# M217X.net
KiCad netlist of a schematic drawn in EAGLE
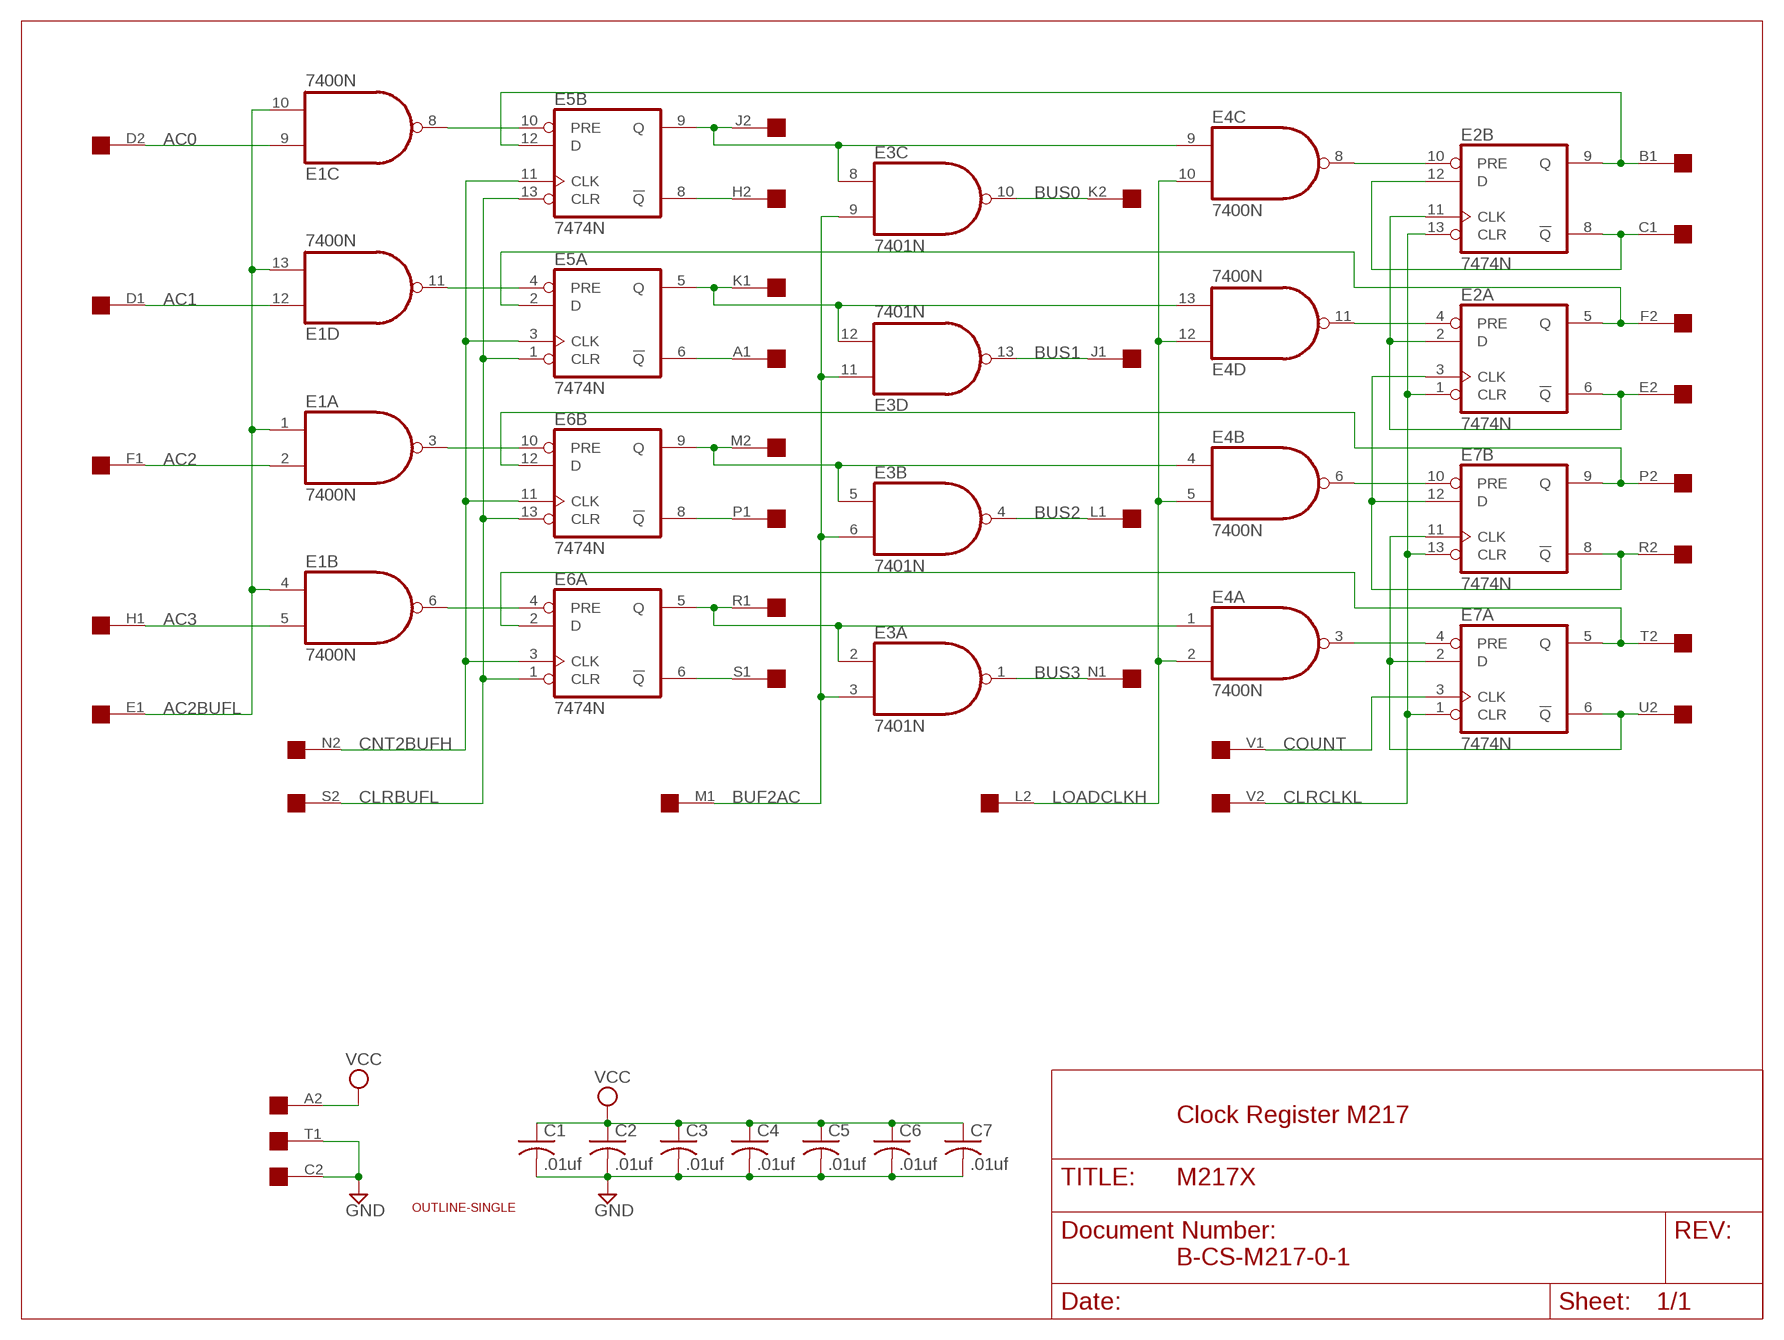
[diagram p0: schematic, sheet 1]

(export (version "E")
  (design (tool "Eeschema 10.0.6"))
  (components
    (comp (ref "C1")
      (value ".01uf")
      (footprint "eagle-import:C050-025X075")
      (libsource (lib "eagle-import") (part "C-US050-025X075"))
    )
    (comp (ref "C2")
      (value ".01uf")
      (footprint "eagle-import:C050-025X075")
      (libsource (lib "eagle-import") (part "C-US050-025X075"))
    )
    (comp (ref "C3")
      (value ".01uf")
      (footprint "eagle-import:C050-025X075")
      (libsource (lib "eagle-import") (part "C-US050-025X075"))
    )
    (comp (ref "C4")
      (value ".01uf")
      (footprint "eagle-import:C050-025X075")
      (libsource (lib "eagle-import") (part "C-US050-025X075"))
    )
    (comp (ref "C5")
      (value ".01uf")
      (footprint "eagle-import:C050-025X075")
      (libsource (lib "eagle-import") (part "C-US050-025X075"))
    )
    (comp (ref "C6")
      (value ".01uf")
      (footprint "eagle-import:C050-025X075")
      (libsource (lib "eagle-import") (part "C-US050-025X075"))
    )
    (comp (ref "C7")
      (value ".01uf")
      (footprint "eagle-import:C050-025X075")
      (libsource (lib "eagle-import") (part "C-US050-025X075"))
    )
    (comp (ref "E1")
      (value "7400N")
      (footprint "eagle-import:DIL14")
      (libsource (lib "eagle-import") (part "7400N"))
    )
    (comp (ref "E2")
      (value "7474N")
      (footprint "eagle-import:DIL14")
      (libsource (lib "eagle-import") (part "7474NS"))
    )
    (comp (ref "E3")
      (value "7401N")
      (footprint "eagle-import:DIL14")
      (libsource (lib "eagle-import") (part "7401NLS"))
    )
    (comp (ref "E4")
      (value "7400N")
      (footprint "eagle-import:DIL14")
      (libsource (lib "eagle-import") (part "7400N"))
    )
    (comp (ref "E5")
      (value "7474N")
      (footprint "eagle-import:DIL14")
      (libsource (lib "eagle-import") (part "7474NS"))
    )
    (comp (ref "E6")
      (value "7474N")
      (footprint "eagle-import:DIL14")
      (libsource (lib "eagle-import") (part "7474NS"))
    )
    (comp (ref "E7")
      (value "7474N")
      (footprint "eagle-import:DIL14")
      (libsource (lib "eagle-import") (part "7474NS"))
    )
    (comp (ref "U$1")
      (value "OUTLINE-SINGLE")
      (footprint "eagle-import:SINGLE")
      (libsource (lib "eagle-import") (part "OUTLINE-SINGLE"))
    )
    (comp (ref "U$4")
      (value "SINGLE")
      (footprint "eagle-import:EDGE-CON2")
      (libsource (lib "eagle-import") (part "SINGLE"))
    )
  )
  (nets
    (net (code "1") (name "/AC0") (class "Default")
      (node (ref "E1") (pin "9") (pinfunction "I0_9") (pintype "input"))
      (node (ref "U$4") (pin "D2") (pinfunction "1_D2") (pintype "bidirectional"))
    )
    (net (code "2") (name "/AC1") (class "Default")
      (node (ref "E1") (pin "12") (pinfunction "I0_12") (pintype "input"))
      (node (ref "U$4") (pin "D1") (pinfunction "1_D1") (pintype "bidirectional"))
    )
    (net (code "3") (name "/AC2") (class "Default")
      (node (ref "E1") (pin "2") (pinfunction "I1_2") (pintype "input"))
      (node (ref "U$4") (pin "F1") (pinfunction "1_F1") (pintype "bidirectional"))
    )
    (net (code "4") (name "/AC2BUFL") (class "Default")
      (node (ref "E1") (pin "1") (pinfunction "I0_1") (pintype "input"))
      (node (ref "E1") (pin "10") (pinfunction "I1_10") (pintype "input"))
      (node (ref "E1") (pin "13") (pinfunction "I1_13") (pintype "input"))
      (node (ref "E1") (pin "4") (pinfunction "I0_4") (pintype "input"))
      (node (ref "U$4") (pin "E1") (pinfunction "1_E1") (pintype "bidirectional"))
    )
    (net (code "5") (name "/AC3") (class "Default")
      (node (ref "E1") (pin "5") (pinfunction "I1_5") (pintype "input"))
      (node (ref "U$4") (pin "H1") (pinfunction "1_H1") (pintype "bidirectional"))
    )
    (net (code "6") (name "/BUF2AC") (class "Default")
      (node (ref "E3") (pin "11") (pinfunction "I0_11") (pintype "input"))
      (node (ref "E3") (pin "3") (pinfunction "I1_3") (pintype "input"))
      (node (ref "E3") (pin "6") (pinfunction "I1_6") (pintype "input"))
      (node (ref "E3") (pin "9") (pinfunction "I1_9") (pintype "input"))
      (node (ref "U$4") (pin "M1") (pinfunction "1_M1") (pintype "bidirectional"))
    )
    (net (code "7") (name "/BUS0") (class "Default")
      (node (ref "E3") (pin "10") (pinfunction "O_10") (pintype "open_collector"))
      (node (ref "U$4") (pin "K2") (pinfunction "1_K2") (pintype "bidirectional"))
    )
    (net (code "8") (name "/BUS1") (class "Default")
      (node (ref "E3") (pin "13") (pinfunction "O_13") (pintype "open_collector"))
      (node (ref "U$4") (pin "J1") (pinfunction "1_J1") (pintype "bidirectional"))
    )
    (net (code "9") (name "/BUS2") (class "Default")
      (node (ref "E3") (pin "4") (pinfunction "O_4") (pintype "open_collector"))
      (node (ref "U$4") (pin "L1") (pinfunction "1_L1") (pintype "bidirectional"))
    )
    (net (code "10") (name "/BUS3") (class "Default")
      (node (ref "E3") (pin "1") (pinfunction "O_1") (pintype "open_collector"))
      (node (ref "U$4") (pin "N1") (pinfunction "1_N1") (pintype "bidirectional"))
    )
    (net (code "11") (name "/CLRBUFL") (class "Default")
      (node (ref "E5") (pin "1") (pinfunction "CLR_1") (pintype "input"))
      (node (ref "E5") (pin "13") (pinfunction "CLR_13") (pintype "input"))
      (node (ref "E6") (pin "1") (pinfunction "CLR_1") (pintype "input"))
      (node (ref "E6") (pin "13") (pinfunction "CLR_13") (pintype "input"))
      (node (ref "U$4") (pin "S2") (pinfunction "1_S2") (pintype "bidirectional"))
    )
    (net (code "12") (name "/CLRCLKL") (class "Default")
      (node (ref "E2") (pin "1") (pinfunction "CLR_1") (pintype "input"))
      (node (ref "E2") (pin "13") (pinfunction "CLR_13") (pintype "input"))
      (node (ref "E7") (pin "1") (pinfunction "CLR_1") (pintype "input"))
      (node (ref "E7") (pin "13") (pinfunction "CLR_13") (pintype "input"))
      (node (ref "U$4") (pin "V2") (pinfunction "1_V2") (pintype "bidirectional"))
    )
    (net (code "13") (name "/CNT2BUFH") (class "Default")
      (node (ref "E5") (pin "11") (pinfunction "CLK_11") (pintype "input"))
      (node (ref "E5") (pin "3") (pinfunction "CLK_3") (pintype "input"))
      (node (ref "E6") (pin "11") (pinfunction "CLK_11") (pintype "input"))
      (node (ref "E6") (pin "3") (pinfunction "CLK_3") (pintype "input"))
      (node (ref "U$4") (pin "N2") (pinfunction "1_N2") (pintype "bidirectional"))
    )
    (net (code "14") (name "/COUNT") (class "Default")
      (node (ref "E7") (pin "3") (pinfunction "CLK_3") (pintype "input"))
      (node (ref "U$4") (pin "V1") (pinfunction "1_V1") (pintype "bidirectional"))
    )
    (net (code "15") (name "/LOADCLKH") (class "Default")
      (node (ref "E4") (pin "10") (pinfunction "I1_10") (pintype "input"))
      (node (ref "E4") (pin "12") (pinfunction "I0_12") (pintype "input"))
      (node (ref "E4") (pin "2") (pinfunction "I1_2") (pintype "input"))
      (node (ref "E4") (pin "5") (pinfunction "I1_5") (pintype "input"))
      (node (ref "U$4") (pin "L2") (pinfunction "1_L2") (pintype "bidirectional"))
    )
    (net (code "16") (name "GND") (class "Default")
      (node (ref "C1") (pin "2") (pinfunction "2_2") (pintype "passive"))
      (node (ref "C2") (pin "2") (pinfunction "2_2") (pintype "passive"))
      (node (ref "C3") (pin "2") (pinfunction "2_2") (pintype "passive"))
      (node (ref "C4") (pin "2") (pinfunction "2_2") (pintype "passive"))
      (node (ref "C5") (pin "2") (pinfunction "2_2") (pintype "passive"))
      (node (ref "C6") (pin "2") (pinfunction "2_2") (pintype "passive"))
      (node (ref "C7") (pin "2") (pinfunction "2_2") (pintype "passive"))
      (node (ref "U$4") (pin "C2") (pinfunction "1_C2") (pintype "bidirectional"))
      (node (ref "U$4") (pin "T1") (pinfunction "1_T1") (pintype "bidirectional"))
    )
    (net (code "17") (name "Net-(E1A-O)") (class "Default")
      (node (ref "E1") (pin "3") (pinfunction "O_3") (pintype "output"))
      (node (ref "E6") (pin "10") (pinfunction "PRE_10") (pintype "input"))
    )
    (net (code "18") (name "Net-(E1B-O)") (class "Default")
      (node (ref "E1") (pin "6") (pinfunction "O_6") (pintype "output"))
      (node (ref "E6") (pin "4") (pinfunction "PRE_4") (pintype "input"))
    )
    (net (code "19") (name "Net-(E1C-O)") (class "Default")
      (node (ref "E1") (pin "8") (pinfunction "O_8") (pintype "output"))
      (node (ref "E5") (pin "10") (pinfunction "PRE_10") (pintype "input"))
    )
    (net (code "20") (name "Net-(E1D-O)") (class "Default")
      (node (ref "E1") (pin "11") (pinfunction "O_11") (pintype "output"))
      (node (ref "E5") (pin "4") (pinfunction "PRE_4") (pintype "input"))
    )
    (net (code "21") (name "Net-(E2A-CLK)") (class "Default")
      (node (ref "E2") (pin "3") (pinfunction "CLK_3") (pintype "input"))
      (node (ref "E7") (pin "12") (pinfunction "D_12") (pintype "input"))
      (node (ref "E7") (pin "8") (pinfunction "~{Q}_8") (pintype "output"))
      (node (ref "U$4") (pin "R2") (pinfunction "1_R2") (pintype "bidirectional"))
    )
    (net (code "22") (name "Net-(E2A-D)") (class "Default")
      (node (ref "E2") (pin "11") (pinfunction "CLK_11") (pintype "input"))
      (node (ref "E2") (pin "2") (pinfunction "D_2") (pintype "input"))
      (node (ref "E2") (pin "6") (pinfunction "~{Q}_6") (pintype "output"))
      (node (ref "U$4") (pin "E2") (pinfunction "1_E2") (pintype "bidirectional"))
    )
    (net (code "23") (name "Net-(E2A-PRE)") (class "Default")
      (node (ref "E2") (pin "4") (pinfunction "PRE_4") (pintype "input"))
      (node (ref "E4") (pin "11") (pinfunction "O_11") (pintype "output"))
    )
    (net (code "24") (name "Net-(E2A-Q)") (class "Default")
      (node (ref "E2") (pin "5") (pinfunction "Q_5") (pintype "output"))
      (node (ref "E5") (pin "2") (pinfunction "D_2") (pintype "input"))
      (node (ref "U$4") (pin "F2") (pinfunction "1_F2") (pintype "bidirectional"))
    )
    (net (code "25") (name "Net-(E2B-D)") (class "Default")
      (node (ref "E2") (pin "12") (pinfunction "D_12") (pintype "input"))
      (node (ref "E2") (pin "8") (pinfunction "~{Q}_8") (pintype "output"))
      (node (ref "U$4") (pin "C1") (pinfunction "1_C1") (pintype "bidirectional"))
    )
    (net (code "26") (name "Net-(E2B-PRE)") (class "Default")
      (node (ref "E2") (pin "10") (pinfunction "PRE_10") (pintype "input"))
      (node (ref "E4") (pin "8") (pinfunction "O_8") (pintype "output"))
    )
    (net (code "27") (name "Net-(E2B-Q)") (class "Default")
      (node (ref "E2") (pin "9") (pinfunction "Q_9") (pintype "output"))
      (node (ref "E5") (pin "12") (pinfunction "D_12") (pintype "input"))
      (node (ref "U$4") (pin "B1") (pinfunction "1_B1") (pintype "bidirectional"))
    )
    (net (code "28") (name "Net-(E3A-I0)") (class "Default")
      (node (ref "E3") (pin "2") (pinfunction "I0_2") (pintype "input"))
      (node (ref "E4") (pin "1") (pinfunction "I0_1") (pintype "input"))
      (node (ref "E6") (pin "5") (pinfunction "Q_5") (pintype "output"))
      (node (ref "U$4") (pin "R1") (pinfunction "1_R1") (pintype "bidirectional"))
    )
    (net (code "29") (name "Net-(E3B-I0)") (class "Default")
      (node (ref "E3") (pin "5") (pinfunction "I0_5") (pintype "input"))
      (node (ref "E4") (pin "4") (pinfunction "I0_4") (pintype "input"))
      (node (ref "E6") (pin "9") (pinfunction "Q_9") (pintype "output"))
      (node (ref "U$4") (pin "M2") (pinfunction "1_M2") (pintype "bidirectional"))
    )
    (net (code "30") (name "Net-(E3C-I0)") (class "Default")
      (node (ref "E3") (pin "8") (pinfunction "I0_8") (pintype "input"))
      (node (ref "E4") (pin "9") (pinfunction "I0_9") (pintype "input"))
      (node (ref "E5") (pin "9") (pinfunction "Q_9") (pintype "output"))
      (node (ref "U$4") (pin "J2") (pinfunction "1_J2") (pintype "bidirectional"))
    )
    (net (code "31") (name "Net-(E3D-I1)") (class "Default")
      (node (ref "E3") (pin "12") (pinfunction "I1_12") (pintype "input"))
      (node (ref "E4") (pin "13") (pinfunction "I1_13") (pintype "input"))
      (node (ref "E5") (pin "5") (pinfunction "Q_5") (pintype "output"))
      (node (ref "U$4") (pin "K1") (pinfunction "1_K1") (pintype "bidirectional"))
    )
    (net (code "32") (name "Net-(E4A-O)") (class "Default")
      (node (ref "E4") (pin "3") (pinfunction "O_3") (pintype "output"))
      (node (ref "E7") (pin "4") (pinfunction "PRE_4") (pintype "input"))
    )
    (net (code "33") (name "Net-(E4B-O)") (class "Default")
      (node (ref "E4") (pin "6") (pinfunction "O_6") (pintype "output"))
      (node (ref "E7") (pin "10") (pinfunction "PRE_10") (pintype "input"))
    )
    (net (code "34") (name "Net-(E5A-~{Q})") (class "Default")
      (node (ref "E5") (pin "6") (pinfunction "~{Q}_6") (pintype "output"))
      (node (ref "U$4") (pin "A1") (pinfunction "1_A1") (pintype "bidirectional"))
    )
    (net (code "35") (name "Net-(E5B-~{Q})") (class "Default")
      (node (ref "E5") (pin "8") (pinfunction "~{Q}_8") (pintype "output"))
      (node (ref "U$4") (pin "H2") (pinfunction "1_H2") (pintype "bidirectional"))
    )
    (net (code "36") (name "Net-(E6A-D)") (class "Default")
      (node (ref "E6") (pin "2") (pinfunction "D_2") (pintype "input"))
      (node (ref "E7") (pin "5") (pinfunction "Q_5") (pintype "output"))
      (node (ref "U$4") (pin "T2") (pinfunction "1_T2") (pintype "bidirectional"))
    )
    (net (code "37") (name "Net-(E6A-~{Q})") (class "Default")
      (node (ref "E6") (pin "6") (pinfunction "~{Q}_6") (pintype "output"))
      (node (ref "U$4") (pin "S1") (pinfunction "1_S1") (pintype "bidirectional"))
    )
    (net (code "38") (name "Net-(E6B-D)") (class "Default")
      (node (ref "E6") (pin "12") (pinfunction "D_12") (pintype "input"))
      (node (ref "E7") (pin "9") (pinfunction "Q_9") (pintype "output"))
      (node (ref "U$4") (pin "P2") (pinfunction "1_P2") (pintype "bidirectional"))
    )
    (net (code "39") (name "Net-(E6B-~{Q})") (class "Default")
      (node (ref "E6") (pin "8") (pinfunction "~{Q}_8") (pintype "output"))
      (node (ref "U$4") (pin "P1") (pinfunction "1_P1") (pintype "bidirectional"))
    )
    (net (code "40") (name "Net-(E7A-D)") (class "Default")
      (node (ref "E7") (pin "11") (pinfunction "CLK_11") (pintype "input"))
      (node (ref "E7") (pin "2") (pinfunction "D_2") (pintype "input"))
      (node (ref "E7") (pin "6") (pinfunction "~{Q}_6") (pintype "output"))
      (node (ref "U$4") (pin "U2") (pinfunction "1_U2") (pintype "bidirectional"))
    )
    (net (code "41") (name "VCC") (class "Default")
      (node (ref "C1") (pin "1") (pinfunction "1_1") (pintype "passive"))
      (node (ref "C2") (pin "1") (pinfunction "1_1") (pintype "passive"))
      (node (ref "C3") (pin "1") (pinfunction "1_1") (pintype "passive"))
      (node (ref "C4") (pin "1") (pinfunction "1_1") (pintype "passive"))
      (node (ref "C5") (pin "1") (pinfunction "1_1") (pintype "passive"))
      (node (ref "C6") (pin "1") (pinfunction "1_1") (pintype "passive"))
      (node (ref "C7") (pin "1") (pinfunction "1_1") (pintype "passive"))
      (node (ref "U$4") (pin "A2") (pinfunction "1_A2") (pintype "bidirectional"))
    )
  )
)
